# Laundry_Switch.net
KiCad netlist of a schematic drawn in EAGLE
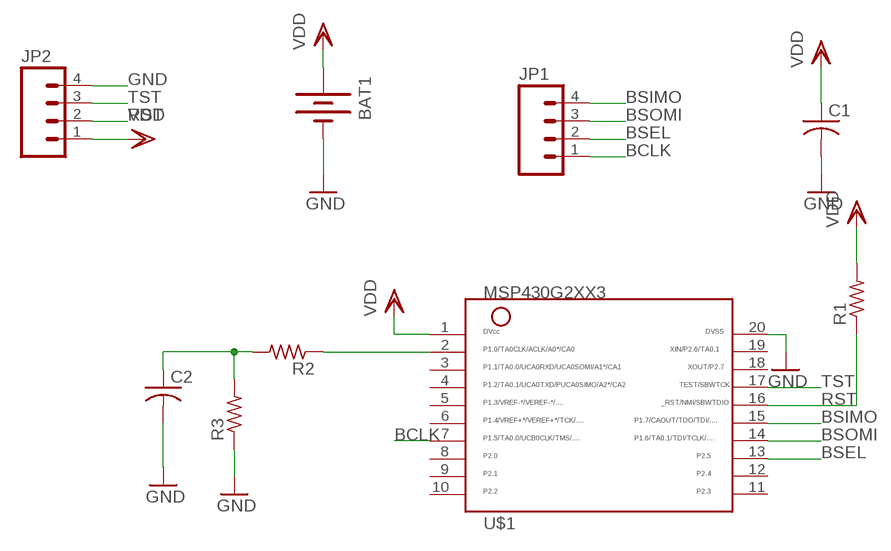
[diagram p0: schematic, sheet 1]

(export (version "E")
  (design (tool "Eeschema 10.0.6"))
  (components
    (comp (ref "BAT1")
      (value "BATTERYBU2032SM")
      (footprint "eagle-import:BU2032SM")
      (libsource (lib "eagle-import") (part "BATTERYBU2032SM"))
    )
    (comp (ref "C1")
      (value "RCL_C-USC1206")
      (footprint "eagle-import:RCL_C1206")
      (libsource (lib "eagle-import") (part "RCL_C-USC1206"))
    )
    (comp (ref "C2")
      (value "C-US050-050X075")
      (footprint "eagle-import:C050-050X075")
      (libsource (lib "eagle-import") (part "C-US050-050X075"))
    )
    (comp (ref "JP1")
      (value "PENDANT_M04LOCK")
      (footprint "eagle-import:PENDANT_1X04_LOCK")
      (libsource (lib "eagle-import") (part "PENDANT_M04LOCK"))
    )
    (comp (ref "JP2")
      (value "PENDANT_M04LOCK")
      (footprint "eagle-import:PENDANT_1X04_LOCK")
      (libsource (lib "eagle-import") (part "PENDANT_M04LOCK"))
    )
    (comp (ref "R1")
      (value "RCL_R-US_R1206")
      (footprint "eagle-import:RCL_R1206")
      (libsource (lib "eagle-import") (part "RCL_R-US_R1206"))
    )
    (comp (ref "R2")
      (value "RCL_R-US_R1206")
      (footprint "eagle-import:RCL_R1206")
      (libsource (lib "eagle-import") (part "RCL_R-US_R1206"))
    )
    (comp (ref "R3")
      (value "RCL_R-US_R1206")
      (footprint "eagle-import:RCL_R1206")
      (libsource (lib "eagle-import") (part "RCL_R-US_R1206"))
    )
    (comp (ref "U$1")
      (value "MSP430G2XX3TSSOP")
      (footprint "eagle-import:PW20")
      (libsource (lib "eagle-import") (part "MSP430G2XX3TSSOP"))
    )
  )
  (nets
    (net (code "1") (name "/BCLK") (class "Default")
      (node (ref "JP1") (pin "1") (pinfunction "1_1") (pintype "passive"))
      (node (ref "U$1") (pin "7") (pinfunction "7_7") (pintype "bidirectional"))
    )
    (net (code "2") (name "/BSEL") (class "Default")
      (node (ref "JP1") (pin "2") (pinfunction "2_2") (pintype "passive"))
      (node (ref "U$1") (pin "13") (pinfunction "13_13") (pintype "bidirectional"))
    )
    (net (code "3") (name "/BSIMO") (class "Default")
      (node (ref "JP1") (pin "4") (pinfunction "4_4") (pintype "passive"))
      (node (ref "U$1") (pin "15") (pinfunction "15_15") (pintype "bidirectional"))
    )
    (net (code "4") (name "/BSOMI") (class "Default")
      (node (ref "JP1") (pin "3") (pinfunction "3_3") (pintype "passive"))
      (node (ref "U$1") (pin "14") (pinfunction "14_14") (pintype "bidirectional"))
    )
    (net (code "5") (name "/RST") (class "Default")
      (node (ref "JP2") (pin "2") (pinfunction "2_2") (pintype "passive"))
      (node (ref "R1") (pin "1") (pinfunction "1_1") (pintype "passive"))
      (node (ref "U$1") (pin "16") (pinfunction "16_16") (pintype "bidirectional"))
    )
    (net (code "6") (name "/TST") (class "Default")
      (node (ref "JP2") (pin "3") (pinfunction "3_3") (pintype "passive"))
      (node (ref "U$1") (pin "17") (pinfunction "17_17") (pintype "bidirectional"))
    )
    (net (code "7") (name "GND") (class "Default")
      (node (ref "BAT1") (pin "P$2") (pinfunction "-_P$2") (pintype "power_in"))
      (node (ref "C1") (pin "2") (pinfunction "2_2") (pintype "passive"))
      (node (ref "C2") (pin "2") (pinfunction "2_2") (pintype "passive"))
      (node (ref "JP2") (pin "4") (pinfunction "4_4") (pintype "passive"))
      (node (ref "R3") (pin "1") (pinfunction "1_1") (pintype "passive"))
      (node (ref "U$1") (pin "20") (pinfunction "20_20") (pintype "bidirectional"))
    )
    (net (code "8") (name "Net-(C2-Pad1)") (class "Default")
      (node (ref "C2") (pin "1") (pinfunction "1_1") (pintype "passive"))
      (node (ref "R2") (pin "2") (pinfunction "2_2") (pintype "passive"))
      (node (ref "R3") (pin "2") (pinfunction "2_2") (pintype "passive"))
    )
    (net (code "9") (name "Net-(R2-Pad1)") (class "Default")
      (node (ref "R2") (pin "1") (pinfunction "1_1") (pintype "passive"))
      (node (ref "U$1") (pin "2") (pinfunction "2_2") (pintype "bidirectional"))
    )
    (net (code "10") (name "VDD") (class "Default")
      (node (ref "BAT1") (pin "P$1") (pinfunction "+_P$1") (pintype "power_in"))
      (node (ref "C1") (pin "1") (pinfunction "1_1") (pintype "passive"))
      (node (ref "JP2") (pin "1") (pinfunction "1_1") (pintype "passive"))
      (node (ref "R1") (pin "2") (pinfunction "2_2") (pintype "passive"))
      (node (ref "U$1") (pin "1") (pinfunction "1_1") (pintype "bidirectional"))
    )
    (net (code "11") (name "unconnected-(U$1-Pad3)") (class "Default")
      (node (ref "U$1") (pin "3") (pinfunction "3_3") (pintype "bidirectional"))
    )
    (net (code "12") (name "unconnected-(U$1-Pad4)") (class "Default")
      (node (ref "U$1") (pin "4") (pinfunction "4_4") (pintype "bidirectional"))
    )
    (net (code "13") (name "unconnected-(U$1-Pad5)") (class "Default")
      (node (ref "U$1") (pin "5") (pinfunction "5_5") (pintype "bidirectional"))
    )
    (net (code "14") (name "unconnected-(U$1-Pad6)") (class "Default")
      (node (ref "U$1") (pin "6") (pinfunction "6_6") (pintype "bidirectional"))
    )
    (net (code "15") (name "unconnected-(U$1-Pad8)") (class "Default")
      (node (ref "U$1") (pin "8") (pinfunction "8_8") (pintype "bidirectional"))
    )
    (net (code "16") (name "unconnected-(U$1-Pad9)") (class "Default")
      (node (ref "U$1") (pin "9") (pinfunction "9_9") (pintype "bidirectional"))
    )
    (net (code "17") (name "unconnected-(U$1-Pad10)") (class "Default")
      (node (ref "U$1") (pin "10") (pinfunction "10_10") (pintype "bidirectional"))
    )
    (net (code "18") (name "unconnected-(U$1-Pad11)") (class "Default")
      (node (ref "U$1") (pin "11") (pinfunction "11_11") (pintype "bidirectional"))
    )
    (net (code "19") (name "unconnected-(U$1-Pad12)") (class "Default")
      (node (ref "U$1") (pin "12") (pinfunction "12_12") (pintype "bidirectional"))
    )
    (net (code "20") (name "unconnected-(U$1-Pad18)") (class "Default")
      (node (ref "U$1") (pin "18") (pinfunction "18_18") (pintype "bidirectional"))
    )
    (net (code "21") (name "unconnected-(U$1-Pad19)") (class "Default")
      (node (ref "U$1") (pin "19") (pinfunction "19_19") (pintype "bidirectional"))
    )
  )
)
